# SCH_Lighting-Strip_2026-09-21_1.net
KiCad netlist of a schematic drawn in EasyEDA
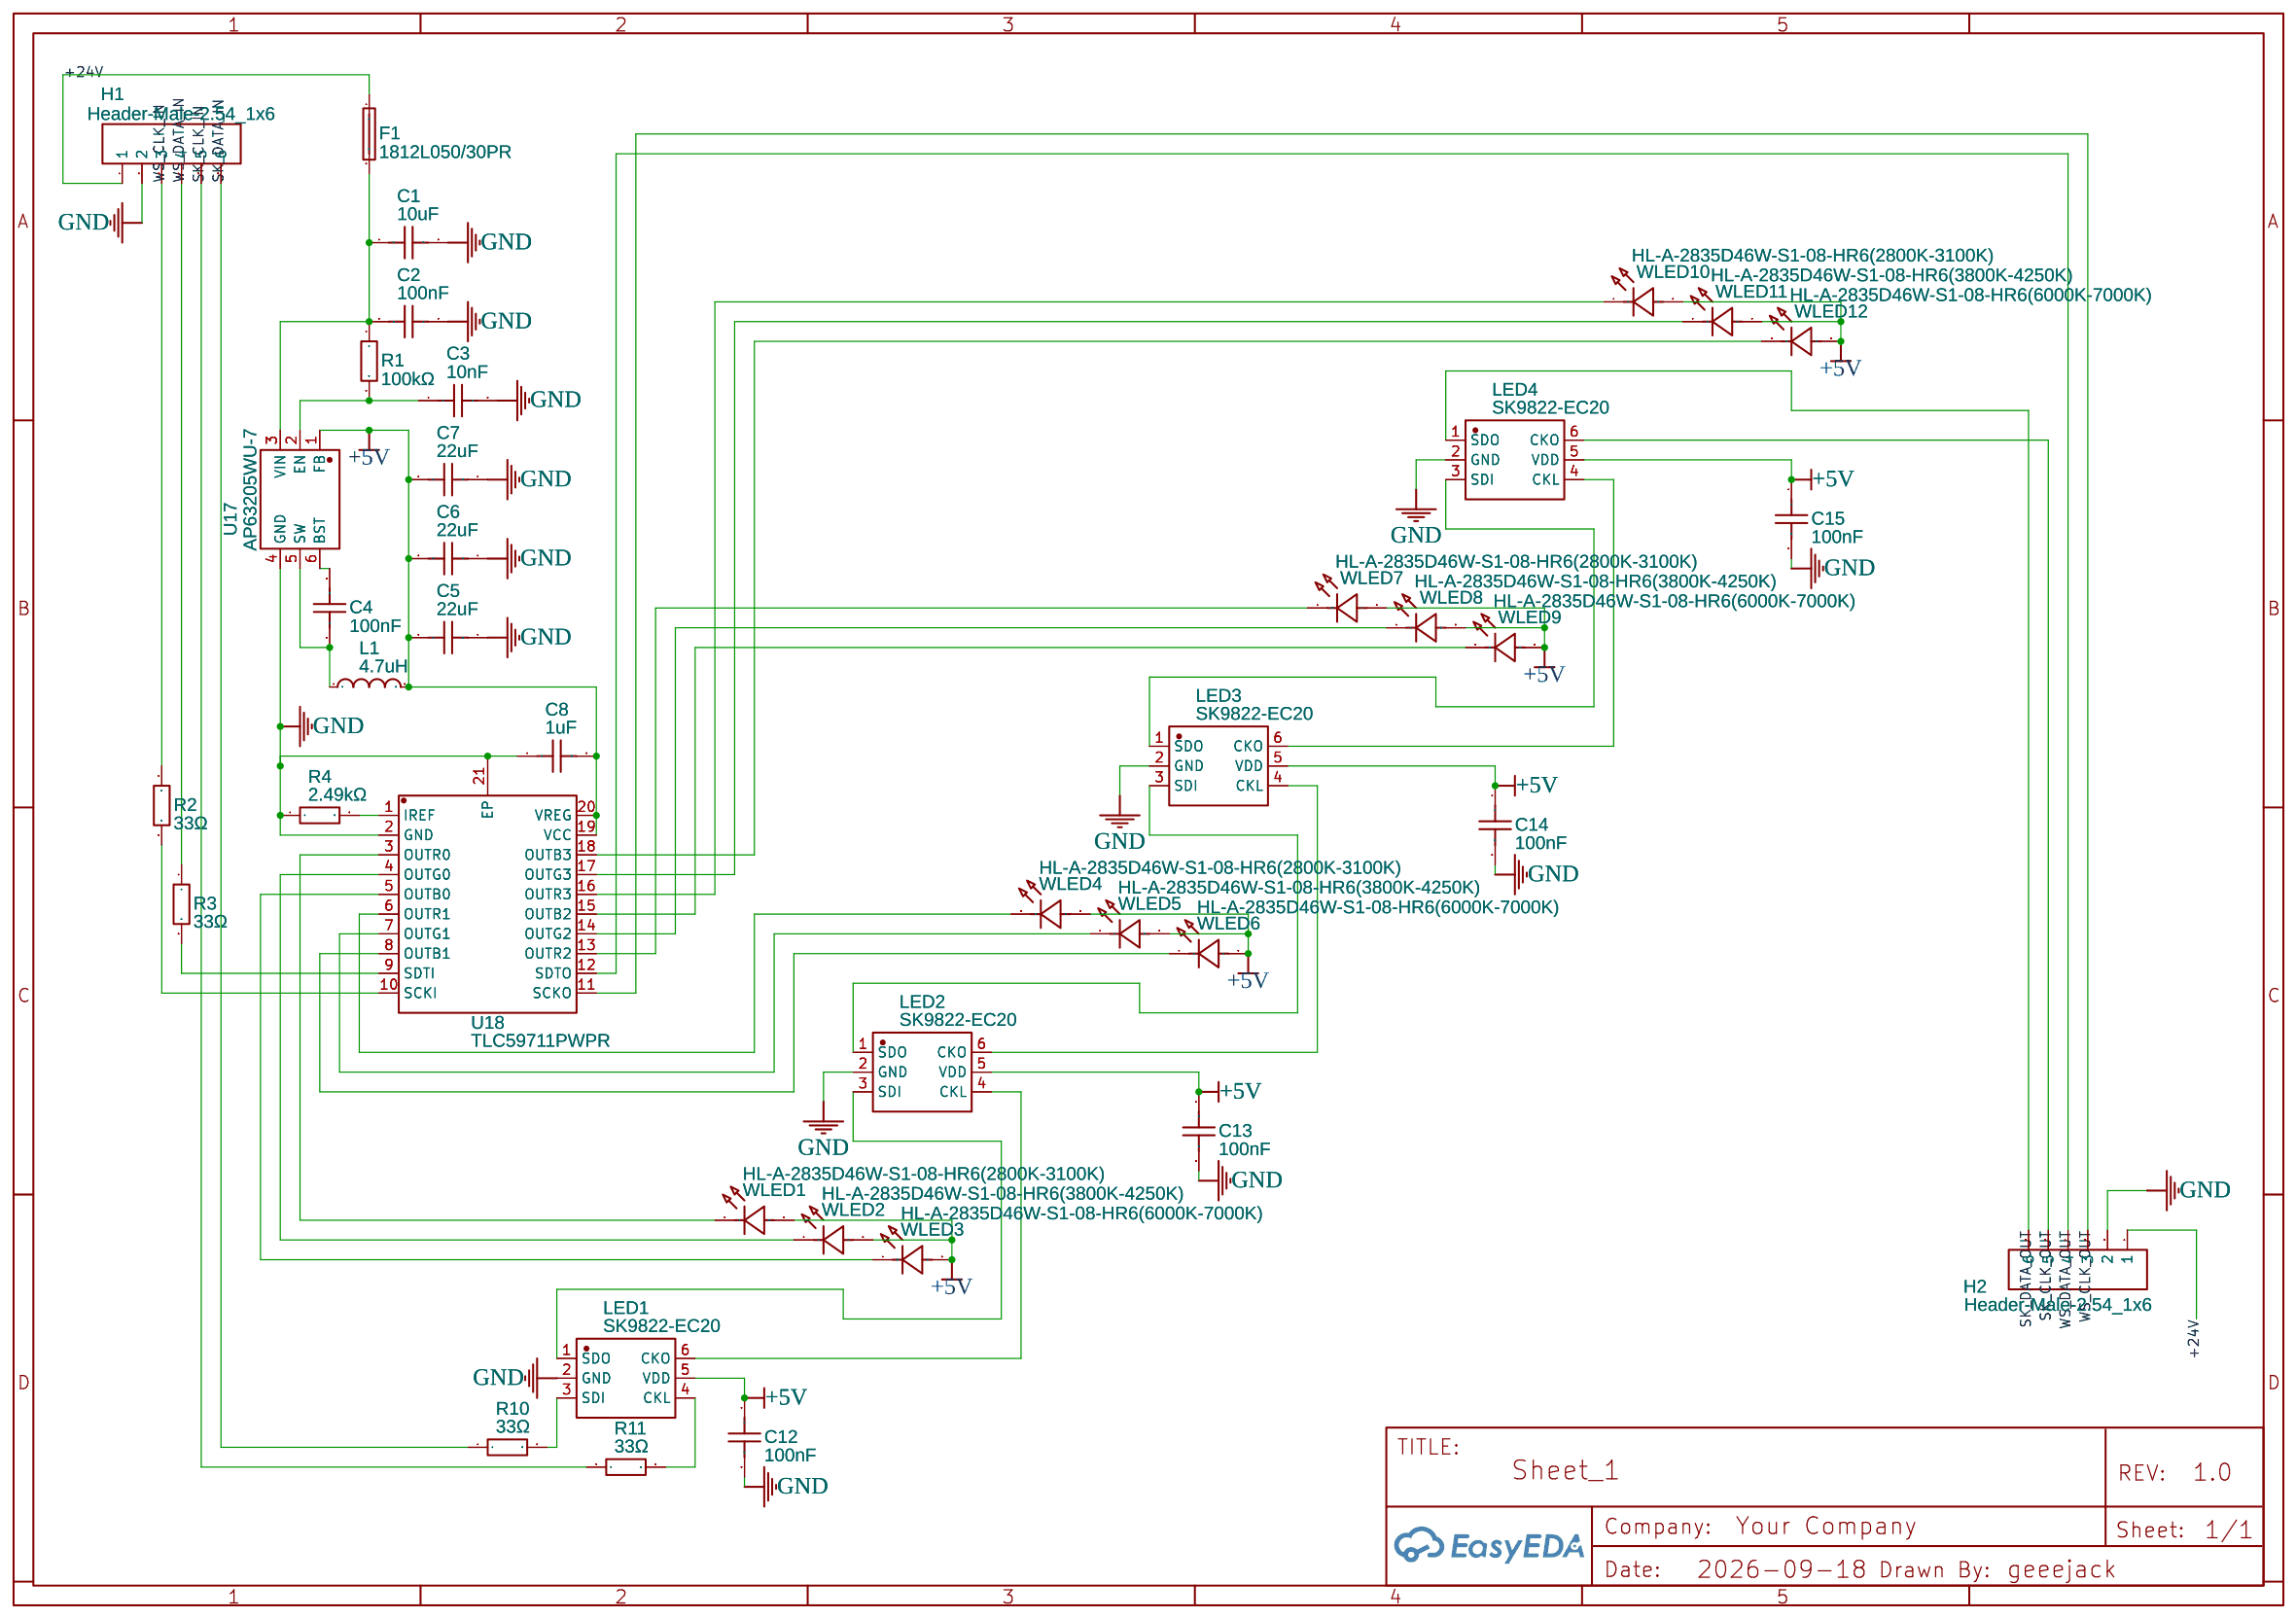
[diagram p0: schematic sheet]

(export (version "E")
  (design (tool "Eeschema 10.0.6"))
  (components
    (comp (ref "C1")
      (value "10uF")
      (fields
        (field (name "Manufacturer Part") "CL32B106KBJNNNE")
        (field (name "Manufacturer") "SAMSUNG(三星)")
      )
      (libsource (lib "") (part "CL32B106KBJNNNE"))
    )
    (comp (ref "C2")
      (value "100nF")
      (fields
        (field (name "Manufacturer Part") "CC0603KRX7R9BB104")
        (field (name "Manufacturer") "YAGEO(国巨)")
      )
      (libsource (lib "") (part "CC0603KRX7R9BB104_1"))
    )
    (comp (ref "C3")
      (value "10nF")
      (fields (field (name "Manufacturer Part") "0603B103K500NT") (field (name "Manufacturer") "FH(风华)"))
      (libsource (lib "") (part "0603B103K500NT"))
    )
    (comp (ref "C4")
      (value "100nF")
      (fields
        (field (name "Manufacturer Part") "CC0603KRX7R9BB104")
        (field (name "Manufacturer") "YAGEO(国巨)")
      )
      (libsource (lib "") (part "CC0603KRX7R9BB104_2"))
    )
    (comp (ref "C5")
      (value "22uF")
      (fields
        (field (name "Manufacturer Part") "CL21A226MAQNNNE")
        (field (name "Manufacturer") "SAMSUNG(三星)")
      )
      (libsource (lib "") (part "CL21A226MAQNNNE"))
    )
    (comp (ref "C6")
      (value "22uF")
      (fields
        (field (name "Manufacturer Part") "CL21A226MAQNNNE")
        (field (name "Manufacturer") "SAMSUNG(三星)")
      )
      (libsource (lib "") (part "CL21A226MAQNNNE"))
    )
    (comp (ref "C7")
      (value "22uF")
      (fields
        (field (name "Manufacturer Part") "CL21A226MAQNNNE")
        (field (name "Manufacturer") "SAMSUNG(三星)")
      )
      (libsource (lib "") (part "CL21A226MAQNNNE"))
    )
    (comp (ref "C8")
      (value "1uF")
      (fields
        (field (name "Manufacturer Part") "CL10A105KB8NNNC")
        (field (name "Manufacturer") "SAMSUNG(三星)")
      )
      (libsource (lib "") (part "CL10A105KB8NNNC"))
    )
    (comp (ref "C12")
      (value "100nF")
      (fields
        (field (name "Manufacturer Part") "CC0603KRX7R9BB104")
        (field (name "Manufacturer") "YAGEO(国巨)")
      )
      (libsource (lib "") (part "CC0603KRX7R9BB104"))
    )
    (comp (ref "C13")
      (value "100nF")
      (fields
        (field (name "Manufacturer Part") "CC0603KRX7R9BB104")
        (field (name "Manufacturer") "YAGEO(国巨)")
      )
      (libsource (lib "") (part "CC0603KRX7R9BB104"))
    )
    (comp (ref "C14")
      (value "100nF")
      (fields
        (field (name "Manufacturer Part") "CC0603KRX7R9BB104")
        (field (name "Manufacturer") "YAGEO(国巨)")
      )
      (libsource (lib "") (part "CC0603KRX7R9BB104"))
    )
    (comp (ref "C15")
      (value "100nF")
      (fields
        (field (name "Manufacturer Part") "CC0603KRX7R9BB104")
        (field (name "Manufacturer") "YAGEO(国巨)")
      )
      (libsource (lib "") (part "CC0603KRX7R9BB104"))
    )
    (comp (ref "F1")
      (value "1812L050/30PR")
      (fields (field (name "Manufacturer") "Littelfuse(美国力特)"))
      (libsource (lib "") (part "1812L050/30PR"))
    )
    (comp (ref "H1")
      (value "Header-Male-2.54_1x6")
      (fields (field (name "Manufacturer Part") "2.54-1x6P直针") (field (name "Manufacturer") "BOOMELE(博穆精密)"))
      (libsource (lib "") (part "Header-Male-2.54_1x6"))
    )
    (comp (ref "H2")
      (value "Header-Male-2.54_1x6")
      (fields (field (name "Manufacturer Part") "2.54-1x6P直针") (field (name "Manufacturer") "BOOMELE(博穆精密)"))
      (libsource (lib "") (part "Header-Male-2.54_1x6_1"))
    )
    (comp (ref "L1")
      (value "4.7uH")
      (fields (field (name "Manufacturer Part") "SWPA5040S4R7NT") (field (name "Manufacturer") "Sunlord(顺络)"))
      (libsource (lib "") (part "SWPA5040S4R7NT"))
    )
    (comp (ref "LED1")
      (value "SK9822-EC20")
      (fields (field (name "Manufacturer") "OPSCO(欧思科)"))
      (libsource (lib "") (part "SK9822-EC20"))
    )
    (comp (ref "LED2")
      (value "SK9822-EC20")
      (fields (field (name "Manufacturer") "OPSCO(欧思科)"))
      (libsource (lib "") (part "SK9822-EC20"))
    )
    (comp (ref "LED3")
      (value "SK9822-EC20")
      (fields (field (name "Manufacturer") "OPSCO(欧思科)"))
      (libsource (lib "") (part "SK9822-EC20"))
    )
    (comp (ref "LED4")
      (value "SK9822-EC20")
      (fields (field (name "Manufacturer") "OPSCO(欧思科)"))
      (libsource (lib "") (part "SK9822-EC20"))
    )
    (comp (ref "R1")
      (value "100kΩ")
      (fields
        (field (name "Manufacturer Part") "0603WAF1003T5E")
        (field (name "Manufacturer") "UNI-ROYAL(厚声)")
      )
      (libsource (lib "") (part "0603WAF1003T5E"))
    )
    (comp (ref "R2")
      (value "33Ω")
      (fields
        (field (name "Manufacturer Part") "0603WAF330JT5E")
        (field (name "Manufacturer") "UNI-ROYAL(厚声)")
      )
      (libsource (lib "") (part "0603WAF330JT5E_1"))
    )
    (comp (ref "R3")
      (value "33Ω")
      (fields
        (field (name "Manufacturer Part") "0603WAF330JT5E")
        (field (name "Manufacturer") "UNI-ROYAL(厚声)")
      )
      (libsource (lib "") (part "0603WAF330JT5E_1"))
    )
    (comp (ref "R4")
      (value "2.49kΩ")
      (fields
        (field (name "Manufacturer Part") "0603WAF2491T5E")
        (field (name "Manufacturer") "UNI-ROYAL(厚声)")
      )
      (libsource (lib "") (part "0603WAF2491T5E"))
    )
    (comp (ref "R10")
      (value "33Ω")
      (fields
        (field (name "Manufacturer Part") "0603WAF330JT5E")
        (field (name "Manufacturer") "UNI-ROYAL(厚声)")
      )
      (libsource (lib "") (part "0603WAF330JT5E"))
    )
    (comp (ref "R11")
      (value "33Ω")
      (fields
        (field (name "Manufacturer Part") "0603WAF330JT5E")
        (field (name "Manufacturer") "UNI-ROYAL(厚声)")
      )
      (libsource (lib "") (part "0603WAF330JT5E"))
    )
    (comp (ref "U17")
      (value "AP63205WU-7")
      (fields (field (name "Manufacturer") "DIODES(美台)"))
      (libsource (lib "") (part "AP63205WU-7"))
    )
    (comp (ref "U18")
      (value "TLC59711PWPR")
      (fields (field (name "Manufacturer") "TI(德州仪器)"))
      (libsource (lib "") (part "TLC59711PWPR"))
    )
    (comp (ref "WLED1")
      (value "HL-A-2835D46W-S1-08-HR6(2800K-3100K)")
      (fields (field (name "Manufacturer") "HONGLITRONIC(鸿利光电)"))
      (libsource (lib "") (part "HL-A-2835D46W-S1-08-HR6(2800K-3100K)"))
    )
    (comp (ref "WLED2")
      (value "HL-A-2835D46W-S1-08-HR6(3800K-4250K)")
      (fields (field (name "Manufacturer") "HONGLITRONIC(鸿利光电)"))
      (libsource (lib "") (part "HL-A-2835D46W-S1-08-HR6(3800K-4250K)"))
    )
    (comp (ref "WLED3")
      (value "HL-A-2835D46W-S1-08-HR6(6000K-7000K)")
      (fields (field (name "Manufacturer") "HONGLITRONIC(鸿利光电)"))
      (libsource (lib "") (part "HL-A-2835D46W-S1-08-HR6(6000K-7000K)"))
    )
    (comp (ref "WLED4")
      (value "HL-A-2835D46W-S1-08-HR6(2800K-3100K)")
      (fields (field (name "Manufacturer") "HONGLITRONIC(鸿利光电)"))
      (libsource (lib "") (part "HL-A-2835D46W-S1-08-HR6(2800K-3100K)"))
    )
    (comp (ref "WLED5")
      (value "HL-A-2835D46W-S1-08-HR6(3800K-4250K)")
      (fields (field (name "Manufacturer") "HONGLITRONIC(鸿利光电)"))
      (libsource (lib "") (part "HL-A-2835D46W-S1-08-HR6(3800K-4250K)"))
    )
    (comp (ref "WLED6")
      (value "HL-A-2835D46W-S1-08-HR6(6000K-7000K)")
      (fields (field (name "Manufacturer") "HONGLITRONIC(鸿利光电)"))
      (libsource (lib "") (part "HL-A-2835D46W-S1-08-HR6(6000K-7000K)"))
    )
    (comp (ref "WLED7")
      (value "HL-A-2835D46W-S1-08-HR6(2800K-3100K)")
      (fields (field (name "Manufacturer") "HONGLITRONIC(鸿利光电)"))
      (libsource (lib "") (part "HL-A-2835D46W-S1-08-HR6(2800K-3100K)"))
    )
    (comp (ref "WLED8")
      (value "HL-A-2835D46W-S1-08-HR6(3800K-4250K)")
      (fields (field (name "Manufacturer") "HONGLITRONIC(鸿利光电)"))
      (libsource (lib "") (part "HL-A-2835D46W-S1-08-HR6(3800K-4250K)"))
    )
    (comp (ref "WLED9")
      (value "HL-A-2835D46W-S1-08-HR6(6000K-7000K)")
      (fields (field (name "Manufacturer") "HONGLITRONIC(鸿利光电)"))
      (libsource (lib "") (part "HL-A-2835D46W-S1-08-HR6(6000K-7000K)"))
    )
    (comp (ref "WLED10")
      (value "HL-A-2835D46W-S1-08-HR6(2800K-3100K)")
      (fields (field (name "Manufacturer") "HONGLITRONIC(鸿利光电)"))
      (libsource (lib "") (part "HL-A-2835D46W-S1-08-HR6(2800K-3100K)"))
    )
    (comp (ref "WLED11")
      (value "HL-A-2835D46W-S1-08-HR6(3800K-4250K)")
      (fields (field (name "Manufacturer") "HONGLITRONIC(鸿利光电)"))
      (libsource (lib "") (part "HL-A-2835D46W-S1-08-HR6(3800K-4250K)"))
    )
    (comp (ref "WLED12")
      (value "HL-A-2835D46W-S1-08-HR6(6000K-7000K)")
      (fields (field (name "Manufacturer") "HONGLITRONIC(鸿利光电)"))
      (libsource (lib "") (part "HL-A-2835D46W-S1-08-HR6(6000K-7000K)"))
    )
  )
  (nets
    (net (code "1") (name "+5V") (class "Default")
      (node (ref "C12") (pin "1") (pinfunction "1_1") (pintype "unspecified"))
      (node (ref "C13") (pin "1") (pinfunction "1_1") (pintype "unspecified"))
      (node (ref "C14") (pin "1") (pinfunction "1_1") (pintype "unspecified"))
      (node (ref "C15") (pin "1") (pinfunction "1_1") (pintype "unspecified"))
      (node (ref "C5") (pin "2") (pinfunction "2_2") (pintype "unspecified"))
      (node (ref "C6") (pin "2") (pinfunction "2_2") (pintype "unspecified"))
      (node (ref "C7") (pin "2") (pinfunction "2_2") (pintype "unspecified"))
      (node (ref "C8") (pin "2") (pinfunction "2_2") (pintype "unspecified"))
      (node (ref "L1") (pin "2") (pinfunction "2_2") (pintype "unspecified"))
      (node (ref "LED1") (pin "5") (pinfunction "VDD_5") (pintype "unspecified"))
      (node (ref "LED2") (pin "5") (pinfunction "VDD_5") (pintype "unspecified"))
      (node (ref "LED3") (pin "5") (pinfunction "VDD_5") (pintype "unspecified"))
      (node (ref "LED4") (pin "5") (pinfunction "VDD_5") (pintype "unspecified"))
      (node (ref "U17") (pin "1") (pinfunction "FB_1") (pintype "unspecified"))
      (node (ref "U18") (pin "19") (pinfunction "VCC_19") (pintype "unspecified"))
      (node (ref "U18") (pin "20") (pinfunction "VREG_20") (pintype "unspecified"))
      (node (ref "WLED1") (pin "2") (pinfunction "A_2") (pintype "unspecified"))
      (node (ref "WLED10") (pin "2") (pinfunction "A_2") (pintype "unspecified"))
      (node (ref "WLED11") (pin "2") (pinfunction "A_2") (pintype "unspecified"))
      (node (ref "WLED12") (pin "2") (pinfunction "A_2") (pintype "unspecified"))
      (node (ref "WLED2") (pin "2") (pinfunction "A_2") (pintype "unspecified"))
      (node (ref "WLED3") (pin "2") (pinfunction "A_2") (pintype "unspecified"))
      (node (ref "WLED4") (pin "2") (pinfunction "A_2") (pintype "unspecified"))
      (node (ref "WLED5") (pin "2") (pinfunction "A_2") (pintype "unspecified"))
      (node (ref "WLED6") (pin "2") (pinfunction "A_2") (pintype "unspecified"))
      (node (ref "WLED7") (pin "2") (pinfunction "A_2") (pintype "unspecified"))
      (node (ref "WLED8") (pin "2") (pinfunction "A_2") (pintype "unspecified"))
      (node (ref "WLED9") (pin "2") (pinfunction "A_2") (pintype "unspecified"))
    )
    (net (code "2") (name "/+24V") (class "Default")
      (node (ref "F1") (pin "1") (pinfunction "1_1") (pintype "unspecified"))
      (node (ref "H1") (pin "1") (pinfunction "1_1") (pintype "input"))
      (node (ref "H2") (pin "1") (pinfunction "1_1") (pintype "input"))
    )
    (net (code "3") (name "/SK_CLK_IN") (class "Default")
      (node (ref "H1") (pin "5") (pinfunction "5_5") (pintype "input"))
      (node (ref "R11") (pin "1") (pinfunction "1_1") (pintype "input"))
    )
    (net (code "4") (name "/SK_CLK_OUT") (class "Default")
      (node (ref "H2") (pin "5") (pinfunction "5_5") (pintype "input"))
      (node (ref "LED4") (pin "6") (pinfunction "CKO_6") (pintype "unspecified"))
    )
    (net (code "5") (name "/SK_DATA_IN") (class "Default")
      (node (ref "H1") (pin "6") (pinfunction "6_6") (pintype "input"))
      (node (ref "R10") (pin "1") (pinfunction "1_1") (pintype "input"))
    )
    (net (code "6") (name "/SK_DATA_OUT") (class "Default")
      (node (ref "H2") (pin "6") (pinfunction "6_6") (pintype "input"))
      (node (ref "LED4") (pin "1") (pinfunction "SDO_1") (pintype "unspecified"))
    )
    (net (code "7") (name "/WS_CLK_IN") (class "Default")
      (node (ref "H1") (pin "3") (pinfunction "3_3") (pintype "input"))
      (node (ref "R2") (pin "1") (pinfunction "1_1") (pintype "input"))
    )
    (net (code "8") (name "/WS_CLK_OUT") (class "Default")
      (node (ref "H2") (pin "3") (pinfunction "3_3") (pintype "input"))
      (node (ref "U18") (pin "11") (pinfunction "SCKO_11") (pintype "unspecified"))
    )
    (net (code "9") (name "/WS_DATA_IN") (class "Default")
      (node (ref "H1") (pin "4") (pinfunction "4_4") (pintype "input"))
      (node (ref "R3") (pin "1") (pinfunction "1_1") (pintype "input"))
    )
    (net (code "10") (name "/WS_DATA_OUT") (class "Default")
      (node (ref "H2") (pin "4") (pinfunction "4_4") (pintype "input"))
      (node (ref "U18") (pin "12") (pinfunction "SDTO_12") (pintype "unspecified"))
    )
    (net (code "11") (name "GND") (class "Default")
      (node (ref "C1") (pin "2") (pinfunction "2_2") (pintype "unspecified"))
      (node (ref "C12") (pin "2") (pinfunction "2_2") (pintype "unspecified"))
      (node (ref "C13") (pin "2") (pinfunction "2_2") (pintype "unspecified"))
      (node (ref "C14") (pin "2") (pinfunction "2_2") (pintype "unspecified"))
      (node (ref "C15") (pin "2") (pinfunction "2_2") (pintype "unspecified"))
      (node (ref "C2") (pin "1") (pinfunction "1_1") (pintype "unspecified"))
      (node (ref "C3") (pin "2") (pinfunction "2_2") (pintype "unspecified"))
      (node (ref "C5") (pin "1") (pinfunction "1_1") (pintype "unspecified"))
      (node (ref "C6") (pin "1") (pinfunction "1_1") (pintype "unspecified"))
      (node (ref "C7") (pin "1") (pinfunction "1_1") (pintype "unspecified"))
      (node (ref "C8") (pin "1") (pinfunction "1_1") (pintype "unspecified"))
      (node (ref "H1") (pin "2") (pinfunction "2_2") (pintype "input"))
      (node (ref "H2") (pin "2") (pinfunction "2_2") (pintype "input"))
      (node (ref "LED1") (pin "2") (pinfunction "GND_2") (pintype "unspecified"))
      (node (ref "LED2") (pin "2") (pinfunction "GND_2") (pintype "unspecified"))
      (node (ref "LED3") (pin "2") (pinfunction "GND_2") (pintype "unspecified"))
      (node (ref "LED4") (pin "2") (pinfunction "GND_2") (pintype "unspecified"))
      (node (ref "R4") (pin "1") (pinfunction "1_1") (pintype "input"))
      (node (ref "U17") (pin "4") (pinfunction "GND_4") (pintype "unspecified"))
      (node (ref "U18") (pin "2") (pinfunction "GND_2") (pintype "unspecified"))
      (node (ref "U18") (pin "21") (pinfunction "EP_21") (pintype "unspecified"))
    )
    (net (code "12") (name "Net-(LED1-CKL)") (class "Default")
      (node (ref "LED1") (pin "4") (pinfunction "CKL_4") (pintype "unspecified"))
      (node (ref "R11") (pin "2") (pinfunction "2_2") (pintype "input"))
    )
    (net (code "13") (name "Net-(LED1-CKO)") (class "Default")
      (node (ref "LED1") (pin "6") (pinfunction "CKO_6") (pintype "unspecified"))
      (node (ref "LED2") (pin "4") (pinfunction "CKL_4") (pintype "unspecified"))
    )
    (net (code "14") (name "Net-(LED1-SDI)") (class "Default")
      (node (ref "LED1") (pin "3") (pinfunction "SDI_3") (pintype "unspecified"))
      (node (ref "R10") (pin "2") (pinfunction "2_2") (pintype "input"))
    )
    (net (code "15") (name "Net-(LED1-SDO)") (class "Default")
      (node (ref "LED1") (pin "1") (pinfunction "SDO_1") (pintype "unspecified"))
      (node (ref "LED2") (pin "3") (pinfunction "SDI_3") (pintype "unspecified"))
    )
    (net (code "16") (name "Net-(LED2-CKO)") (class "Default")
      (node (ref "LED2") (pin "6") (pinfunction "CKO_6") (pintype "unspecified"))
      (node (ref "LED3") (pin "4") (pinfunction "CKL_4") (pintype "unspecified"))
    )
    (net (code "17") (name "Net-(LED2-SDO)") (class "Default")
      (node (ref "LED2") (pin "1") (pinfunction "SDO_1") (pintype "unspecified"))
      (node (ref "LED3") (pin "3") (pinfunction "SDI_3") (pintype "unspecified"))
    )
    (net (code "18") (name "Net-(LED3-CKO)") (class "Default")
      (node (ref "LED3") (pin "6") (pinfunction "CKO_6") (pintype "unspecified"))
      (node (ref "LED4") (pin "4") (pinfunction "CKL_4") (pintype "unspecified"))
    )
    (net (code "19") (name "Net-(LED3-SDO)") (class "Default")
      (node (ref "LED3") (pin "1") (pinfunction "SDO_1") (pintype "unspecified"))
      (node (ref "LED4") (pin "3") (pinfunction "SDI_3") (pintype "unspecified"))
    )
    (net (code "20") (name "Net-(U17-BST)") (class "Default")
      (node (ref "C4") (pin "2") (pinfunction "2_2") (pintype "unspecified"))
      (node (ref "U17") (pin "6") (pinfunction "BST_6") (pintype "unspecified"))
    )
    (net (code "21") (name "Net-(U17-EN)") (class "Default")
      (node (ref "C3") (pin "1") (pinfunction "1_1") (pintype "unspecified"))
      (node (ref "R1") (pin "2") (pinfunction "2_2") (pintype "input"))
      (node (ref "U17") (pin "2") (pinfunction "EN_2") (pintype "unspecified"))
    )
    (net (code "22") (name "Net-(U17-SW)") (class "Default")
      (node (ref "C4") (pin "1") (pinfunction "1_1") (pintype "unspecified"))
      (node (ref "L1") (pin "1") (pinfunction "1_1") (pintype "unspecified"))
      (node (ref "U17") (pin "5") (pinfunction "SW_5") (pintype "unspecified"))
    )
    (net (code "23") (name "Net-(U17-VIN)") (class "Default")
      (node (ref "C1") (pin "1") (pinfunction "1_1") (pintype "unspecified"))
      (node (ref "C2") (pin "2") (pinfunction "2_2") (pintype "unspecified"))
      (node (ref "F1") (pin "2") (pinfunction "2_2") (pintype "unspecified"))
      (node (ref "R1") (pin "1") (pinfunction "1_1") (pintype "input"))
      (node (ref "U17") (pin "3") (pinfunction "VIN_3") (pintype "unspecified"))
    )
    (net (code "24") (name "Net-(U18-IREF)") (class "Default")
      (node (ref "R4") (pin "2") (pinfunction "2_2") (pintype "input"))
      (node (ref "U18") (pin "1") (pinfunction "IREF_1") (pintype "unspecified"))
    )
    (net (code "25") (name "Net-(U18-OUTB0)") (class "Default")
      (node (ref "U18") (pin "5") (pinfunction "OUTB0_5") (pintype "unspecified"))
      (node (ref "WLED3") (pin "1") (pinfunction "C_1") (pintype "unspecified"))
    )
    (net (code "26") (name "Net-(U18-OUTB1)") (class "Default")
      (node (ref "U18") (pin "8") (pinfunction "OUTB1_8") (pintype "unspecified"))
      (node (ref "WLED6") (pin "1") (pinfunction "C_1") (pintype "unspecified"))
    )
    (net (code "27") (name "Net-(U18-OUTB2)") (class "Default")
      (node (ref "U18") (pin "15") (pinfunction "OUTB2_15") (pintype "unspecified"))
      (node (ref "WLED9") (pin "1") (pinfunction "C_1") (pintype "unspecified"))
    )
    (net (code "28") (name "Net-(U18-OUTB3)") (class "Default")
      (node (ref "U18") (pin "18") (pinfunction "OUTB3_18") (pintype "unspecified"))
      (node (ref "WLED12") (pin "1") (pinfunction "C_1") (pintype "unspecified"))
    )
    (net (code "29") (name "Net-(U18-OUTG0)") (class "Default")
      (node (ref "U18") (pin "4") (pinfunction "OUTG0_4") (pintype "unspecified"))
      (node (ref "WLED2") (pin "1") (pinfunction "K_1") (pintype "unspecified"))
    )
    (net (code "30") (name "Net-(U18-OUTG1)") (class "Default")
      (node (ref "U18") (pin "7") (pinfunction "OUTG1_7") (pintype "unspecified"))
      (node (ref "WLED5") (pin "1") (pinfunction "K_1") (pintype "unspecified"))
    )
    (net (code "31") (name "Net-(U18-OUTG2)") (class "Default")
      (node (ref "U18") (pin "14") (pinfunction "OUTG2_14") (pintype "unspecified"))
      (node (ref "WLED8") (pin "1") (pinfunction "K_1") (pintype "unspecified"))
    )
    (net (code "32") (name "Net-(U18-OUTG3)") (class "Default")
      (node (ref "U18") (pin "17") (pinfunction "OUTG3_17") (pintype "unspecified"))
      (node (ref "WLED11") (pin "1") (pinfunction "K_1") (pintype "unspecified"))
    )
    (net (code "33") (name "Net-(U18-OUTR0)") (class "Default")
      (node (ref "U18") (pin "3") (pinfunction "OUTR0_3") (pintype "unspecified"))
      (node (ref "WLED1") (pin "1") (pinfunction "K_1") (pintype "unspecified"))
    )
    (net (code "34") (name "Net-(U18-OUTR1)") (class "Default")
      (node (ref "U18") (pin "6") (pinfunction "OUTR1_6") (pintype "unspecified"))
      (node (ref "WLED4") (pin "1") (pinfunction "K_1") (pintype "unspecified"))
    )
    (net (code "35") (name "Net-(U18-OUTR2)") (class "Default")
      (node (ref "U18") (pin "13") (pinfunction "OUTR2_13") (pintype "unspecified"))
      (node (ref "WLED7") (pin "1") (pinfunction "K_1") (pintype "unspecified"))
    )
    (net (code "36") (name "Net-(U18-OUTR3)") (class "Default")
      (node (ref "U18") (pin "16") (pinfunction "OUTR3_16") (pintype "unspecified"))
      (node (ref "WLED10") (pin "1") (pinfunction "K_1") (pintype "unspecified"))
    )
    (net (code "37") (name "Net-(U18-SCKI)") (class "Default")
      (node (ref "R2") (pin "2") (pinfunction "2_2") (pintype "input"))
      (node (ref "U18") (pin "10") (pinfunction "SCKI_10") (pintype "unspecified"))
    )
    (net (code "38") (name "Net-(U18-SDTI)") (class "Default")
      (node (ref "R3") (pin "2") (pinfunction "2_2") (pintype "input"))
      (node (ref "U18") (pin "9") (pinfunction "SDTI_9") (pintype "unspecified"))
    )
  )
)
